# io2.net
KiCad netlist of a schematic drawn in EAGLE
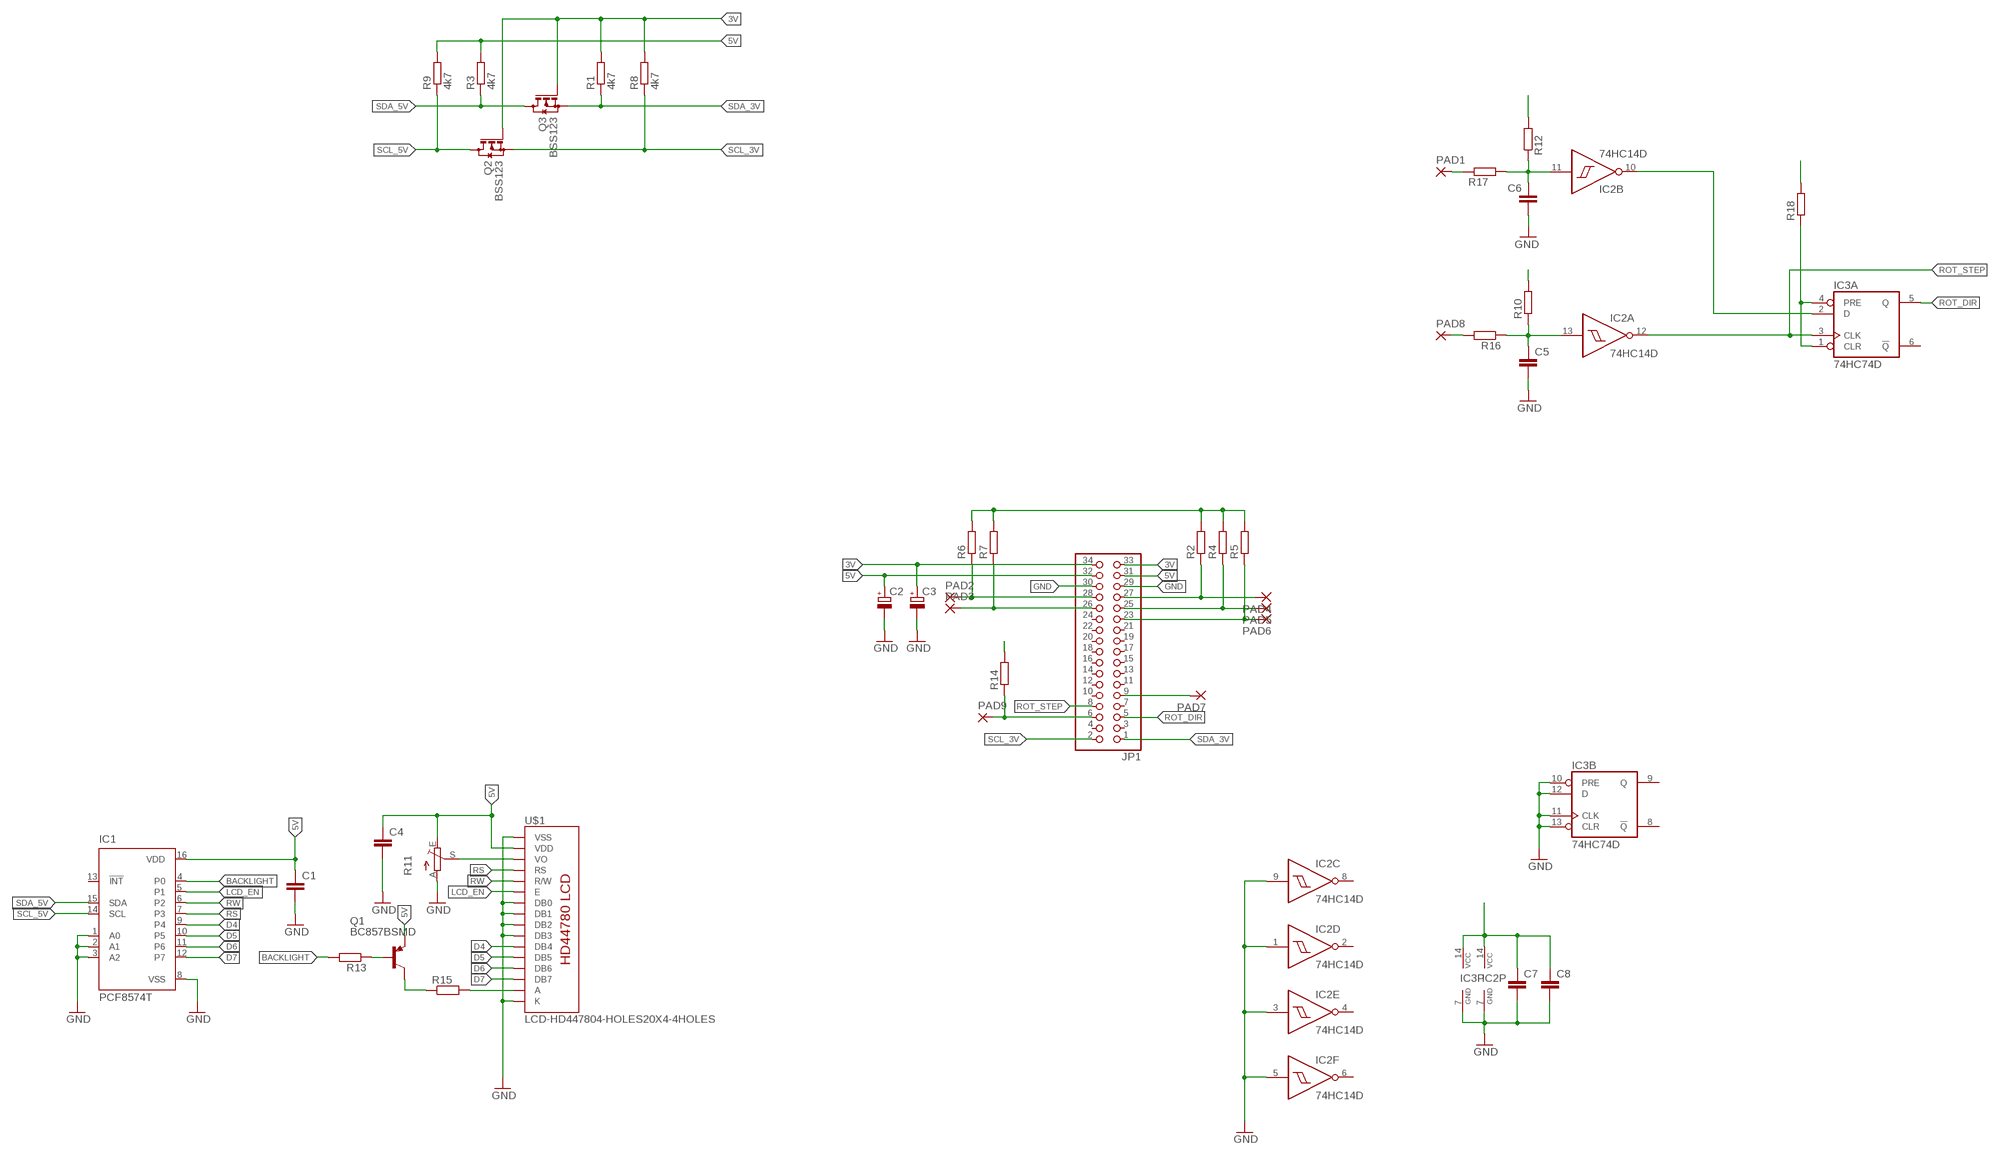
[diagram p0: schematic, sheet 1]

(export (version "E")
  (design (tool "Eeschema 10.0.6"))
  (components
    (comp (ref "C1")
      (value "C-EUC0603")
      (footprint "eagle-import:C0603")
      (libsource (lib "eagle-import") (part "C-EUC0603"))
    )
    (comp (ref "C2")
      (value "CPOL-EUSMCD")
      (footprint "eagle-import:SMC_D")
      (libsource (lib "eagle-import") (part "CPOL-EUSMCD"))
    )
    (comp (ref "C3")
      (value "CPOL-EUSMCB")
      (footprint "eagle-import:SMC_B")
      (libsource (lib "eagle-import") (part "CPOL-EUSMCB"))
    )
    (comp (ref "C4")
      (value "C-EUC1206")
      (footprint "eagle-import:C1206")
      (libsource (lib "eagle-import") (part "C-EUC1206"))
    )
    (comp (ref "C5")
      (value "C-EUC0603")
      (footprint "eagle-import:C0603")
      (libsource (lib "eagle-import") (part "C-EUC0603"))
    )
    (comp (ref "C6")
      (value "C-EUC0603")
      (footprint "eagle-import:C0603")
      (libsource (lib "eagle-import") (part "C-EUC0603"))
    )
    (comp (ref "C7")
      (value "C-EUC0603")
      (footprint "eagle-import:C0603")
      (libsource (lib "eagle-import") (part "C-EUC0603"))
    )
    (comp (ref "C8")
      (value "C-EUC0603")
      (footprint "eagle-import:C0603")
      (libsource (lib "eagle-import") (part "C-EUC0603"))
    )
    (comp (ref "IC1")
      (value "PCF8574T")
      (footprint "eagle-import:SO16W")
      (fields (field (name "MPN") "PCF8574T/3,512"))
      (libsource (lib "eagle-import") (part "PCF8574T"))
    )
    (comp (ref "IC2")
      (value "74HC14D")
      (footprint "eagle-import:SO14")
      (libsource (lib "eagle-import") (part "7414DHC"))
    )
    (comp (ref "IC3")
      (value "74HC74D")
      (footprint "eagle-import:SO14")
      (libsource (lib "eagle-import") (part "7474DHC"))
    )
    (comp (ref "JP1")
      (value "PINHD-2X17_2.54-SMD")
      (footprint "eagle-import:2X17SMD")
      (libsource (lib "eagle-import") (part "PINHD-2X17_2.54-SMD"))
    )
    (comp (ref "PAD1")
      (value "SMD2")
      (footprint "eagle-import:SMD1,27-2,54")
      (libsource (lib "eagle-import") (part "SMD2"))
    )
    (comp (ref "PAD2")
      (value "SMD2")
      (footprint "eagle-import:SMD1,27-2,54")
      (libsource (lib "eagle-import") (part "SMD2"))
    )
    (comp (ref "PAD3")
      (value "SMD2")
      (footprint "eagle-import:SMD1,27-2,54")
      (libsource (lib "eagle-import") (part "SMD2"))
    )
    (comp (ref "PAD4")
      (value "SMD2")
      (footprint "eagle-import:SMD1,27-2,54")
      (libsource (lib "eagle-import") (part "SMD2"))
    )
    (comp (ref "PAD5")
      (value "SMD2")
      (footprint "eagle-import:SMD1,27-2,54")
      (libsource (lib "eagle-import") (part "SMD2"))
    )
    (comp (ref "PAD6")
      (value "SMD2")
      (footprint "eagle-import:SMD1,27-2,54")
      (libsource (lib "eagle-import") (part "SMD2"))
    )
    (comp (ref "PAD7")
      (value "SMD2")
      (footprint "eagle-import:SMD1,27-2,54")
      (libsource (lib "eagle-import") (part "SMD2"))
    )
    (comp (ref "PAD8")
      (value "SMD2")
      (footprint "eagle-import:SMD1,27-2,54")
      (libsource (lib "eagle-import") (part "SMD2"))
    )
    (comp (ref "PAD9")
      (value "SMD2")
      (footprint "eagle-import:SMD1,27-2,54")
      (libsource (lib "eagle-import") (part "SMD2"))
    )
    (comp (ref "Q1")
      (value "BC857BSMD")
      (footprint "eagle-import:SOT23-BEC")
      (libsource (lib "eagle-import") (part "BC857SMDB"))
    )
    (comp (ref "Q2")
      (value "BSS123")
      (footprint "eagle-import:SOT23")
      (libsource (lib "eagle-import") (part "BSS123"))
    )
    (comp (ref "Q3")
      (value "BSS123")
      (footprint "eagle-import:SOT23")
      (libsource (lib "eagle-import") (part "BSS123"))
    )
    (comp (ref "R1")
      (value "4k7")
      (footprint "eagle-import:R0603")
      (libsource (lib "eagle-import") (part "R-EU_R0603"))
    )
    (comp (ref "R2")
      (value "R-EU_0204/7")
      (footprint "eagle-import:0204_7")
      (libsource (lib "eagle-import") (part "R-EU_0204/7"))
    )
    (comp (ref "R3")
      (value "4k7")
      (footprint "eagle-import:R0603")
      (libsource (lib "eagle-import") (part "R-EU_R0603"))
    )
    (comp (ref "R4")
      (value "R-EU_0204/7")
      (footprint "eagle-import:0204_7")
      (libsource (lib "eagle-import") (part "R-EU_0204/7"))
    )
    (comp (ref "R5")
      (value "R-EU_0204/7")
      (footprint "eagle-import:0204_7")
      (libsource (lib "eagle-import") (part "R-EU_0204/7"))
    )
    (comp (ref "R6")
      (value "R-EU_0204/7")
      (footprint "eagle-import:0204_7")
      (libsource (lib "eagle-import") (part "R-EU_0204/7"))
    )
    (comp (ref "R7")
      (value "R-EU_0204/7")
      (footprint "eagle-import:0204_7")
      (libsource (lib "eagle-import") (part "R-EU_0204/7"))
    )
    (comp (ref "R8")
      (value "4k7")
      (footprint "eagle-import:R0603")
      (libsource (lib "eagle-import") (part "R-EU_R0603"))
    )
    (comp (ref "R9")
      (value "4k7")
      (footprint "eagle-import:R0603")
      (libsource (lib "eagle-import") (part "R-EU_R0603"))
    )
    (comp (ref "R10")
      (value "R-EU_0204/7")
      (footprint "eagle-import:0204_7")
      (libsource (lib "eagle-import") (part "R-EU_0204/7"))
    )
    (comp (ref "R11")
      (value "TRIM_EU-B25U")
      (footprint "eagle-import:B25U")
      (libsource (lib "eagle-import") (part "TRIM_EU-B25U"))
    )
    (comp (ref "R12")
      (value "R-EU_0204/7")
      (footprint "eagle-import:0204_7")
      (libsource (lib "eagle-import") (part "R-EU_0204/7"))
    )
    (comp (ref "R13")
      (value "R-EU_0207/12")
      (footprint "eagle-import:0207_12")
      (libsource (lib "eagle-import") (part "R-EU_0207/12"))
    )
    (comp (ref "R14")
      (value "R-EU_0204/5")
      (footprint "eagle-import:0204_5")
      (libsource (lib "eagle-import") (part "R-EU_0204/5"))
    )
    (comp (ref "R15")
      (value "R-EU_R0603")
      (footprint "eagle-import:R0603")
      (libsource (lib "eagle-import") (part "R-EU_R0603"))
    )
    (comp (ref "R16")
      (value "R-EU_R0603")
      (footprint "eagle-import:R0603")
      (libsource (lib "eagle-import") (part "R-EU_R0603"))
    )
    (comp (ref "R17")
      (value "R-EU_R0603")
      (footprint "eagle-import:R0603")
      (libsource (lib "eagle-import") (part "R-EU_R0603"))
    )
    (comp (ref "R18")
      (value "R-EU_0204/7")
      (footprint "eagle-import:0204_7")
      (libsource (lib "eagle-import") (part "R-EU_0204/7"))
    )
    (comp (ref "U$1")
      (value "LCD-HD447804-HOLES20X4-4HOLES")
      (footprint "eagle-import:LCD-20X4-4HOLES")
      (libsource (lib "eagle-import") (part "LCD-HD4478020X4-4HOLES4-HOLES"))
    )
  )
  (nets
    (net (code "1") (name "3V") (class "Default")
      (node (ref "C3") (pin "+") (pinfunction "+_+") (pintype "passive"))
      (node (ref "C7") (pin "1") (pinfunction "1_1") (pintype "passive"))
      (node (ref "C8") (pin "1") (pinfunction "1_1") (pintype "passive"))
      (node (ref "IC2") (pin "14") (pinfunction "VCC_14") (pintype "power_in"))
      (node (ref "IC3") (pin "14") (pinfunction "VCC_14") (pintype "power_in"))
      (node (ref "JP1") (pin "33") (pinfunction "33_33") (pintype "passive"))
      (node (ref "JP1") (pin "34") (pinfunction "34_34") (pintype "passive"))
      (node (ref "Q2") (pin "1") (pinfunction "G_1") (pintype "passive"))
      (node (ref "Q3") (pin "1") (pinfunction "G_1") (pintype "passive"))
      (node (ref "R1") (pin "2") (pinfunction "2_2") (pintype "passive"))
      (node (ref "R10") (pin "2") (pinfunction "2_2") (pintype "passive"))
      (node (ref "R12") (pin "2") (pinfunction "2_2") (pintype "passive"))
      (node (ref "R14") (pin "2") (pinfunction "2_2") (pintype "passive"))
      (node (ref "R18") (pin "2") (pinfunction "2_2") (pintype "passive"))
      (node (ref "R2") (pin "2") (pinfunction "2_2") (pintype "passive"))
      (node (ref "R4") (pin "2") (pinfunction "2_2") (pintype "passive"))
      (node (ref "R5") (pin "2") (pinfunction "2_2") (pintype "passive"))
      (node (ref "R6") (pin "2") (pinfunction "2_2") (pintype "passive"))
      (node (ref "R7") (pin "2") (pinfunction "2_2") (pintype "passive"))
      (node (ref "R8") (pin "2") (pinfunction "2_2") (pintype "passive"))
    )
    (net (code "2") (name "5V") (class "Default")
      (node (ref "C1") (pin "1") (pinfunction "1_1") (pintype "passive"))
      (node (ref "C2") (pin "+") (pinfunction "+_+") (pintype "passive"))
      (node (ref "C4") (pin "1") (pinfunction "1_1") (pintype "passive"))
      (node (ref "IC1") (pin "16") (pinfunction "VDD_16") (pintype "power_in"))
      (node (ref "JP1") (pin "31") (pinfunction "31_31") (pintype "passive"))
      (node (ref "JP1") (pin "32") (pinfunction "32_32") (pintype "passive"))
      (node (ref "Q1") (pin "E") (pinfunction "E_E") (pintype "passive"))
      (node (ref "R11") (pin "E") (pinfunction "E_E") (pintype "passive"))
      (node (ref "R3") (pin "2") (pinfunction "2_2") (pintype "passive"))
      (node (ref "R9") (pin "2") (pinfunction "2_2") (pintype "passive"))
      (node (ref "U$1") (pin "P$2") (pinfunction "VDD_P$2") (pintype "power_in"))
    )
    (net (code "3") (name "BACKLIGHT") (class "Default")
      (node (ref "IC1") (pin "4") (pinfunction "P0_4") (pintype "bidirectional"))
      (node (ref "R13") (pin "2") (pinfunction "2_2") (pintype "passive"))
    )
    (net (code "4") (name "D4") (class "Default")
      (node (ref "IC1") (pin "9") (pinfunction "P4_9") (pintype "bidirectional"))
      (node (ref "U$1") (pin "P$11") (pinfunction "DB4_P$11") (pintype "bidirectional"))
    )
    (net (code "5") (name "D5") (class "Default")
      (node (ref "IC1") (pin "10") (pinfunction "P5_10") (pintype "bidirectional"))
      (node (ref "U$1") (pin "P$12") (pinfunction "DB5_P$12") (pintype "bidirectional"))
    )
    (net (code "6") (name "D6") (class "Default")
      (node (ref "IC1") (pin "11") (pinfunction "P6_11") (pintype "bidirectional"))
      (node (ref "U$1") (pin "P$13") (pinfunction "DB6_P$13") (pintype "bidirectional"))
    )
    (net (code "7") (name "D7") (class "Default")
      (node (ref "IC1") (pin "12") (pinfunction "P7_12") (pintype "bidirectional"))
      (node (ref "U$1") (pin "P$14") (pinfunction "DB7_P$14") (pintype "bidirectional"))
    )
    (net (code "8") (name "GND") (class "Default")
      (node (ref "C1") (pin "2") (pinfunction "2_2") (pintype "passive"))
      (node (ref "C2") (pin "-") (pinfunction "-_-") (pintype "passive"))
      (node (ref "C3") (pin "-") (pinfunction "-_-") (pintype "passive"))
      (node (ref "C4") (pin "2") (pinfunction "2_2") (pintype "passive"))
      (node (ref "C5") (pin "2") (pinfunction "2_2") (pintype "passive"))
      (node (ref "C6") (pin "2") (pinfunction "2_2") (pintype "passive"))
      (node (ref "C7") (pin "2") (pinfunction "2_2") (pintype "passive"))
      (node (ref "C8") (pin "2") (pinfunction "2_2") (pintype "passive"))
      (node (ref "IC1") (pin "1") (pinfunction "A0_1") (pintype "input"))
      (node (ref "IC1") (pin "2") (pinfunction "A1_2") (pintype "input"))
      (node (ref "IC1") (pin "3") (pinfunction "A2_3") (pintype "input"))
      (node (ref "IC1") (pin "8") (pinfunction "VSS_8") (pintype "power_in"))
      (node (ref "IC2") (pin "1") (pinfunction "I_1") (pintype "input"))
      (node (ref "IC2") (pin "3") (pinfunction "I_3") (pintype "input"))
      (node (ref "IC2") (pin "5") (pinfunction "I_5") (pintype "input"))
      (node (ref "IC2") (pin "7") (pinfunction "GND_7") (pintype "power_in"))
      (node (ref "IC2") (pin "9") (pinfunction "I_9") (pintype "input"))
      (node (ref "IC3") (pin "10") (pinfunction "PRE_10") (pintype "input"))
      (node (ref "IC3") (pin "11") (pinfunction "CLK_11") (pintype "input"))
      (node (ref "IC3") (pin "12") (pinfunction "D_12") (pintype "input"))
      (node (ref "IC3") (pin "13") (pinfunction "CLR_13") (pintype "input"))
      (node (ref "IC3") (pin "7") (pinfunction "GND_7") (pintype "power_in"))
      (node (ref "JP1") (pin "29") (pinfunction "29_29") (pintype "passive"))
      (node (ref "JP1") (pin "30") (pinfunction "30_30") (pintype "passive"))
      (node (ref "R11") (pin "A") (pinfunction "A_A") (pintype "passive"))
      (node (ref "U$1") (pin "P$1") (pinfunction "VSS_P$1") (pintype "power_in"))
      (node (ref "U$1") (pin "P$10") (pinfunction "DB3_P$10") (pintype "bidirectional"))
      (node (ref "U$1") (pin "P$16") (pinfunction "K_P$16") (pintype "power_in"))
      (node (ref "U$1") (pin "P$7") (pinfunction "DB0_P$7") (pintype "bidirectional"))
      (node (ref "U$1") (pin "P$8") (pinfunction "DB1_P$8") (pintype "bidirectional"))
      (node (ref "U$1") (pin "P$9") (pinfunction "DB2_P$9") (pintype "bidirectional"))
    )
    (net (code "9") (name "LCD_EN") (class "Default")
      (node (ref "IC1") (pin "5") (pinfunction "P1_5") (pintype "bidirectional"))
      (node (ref "U$1") (pin "P$6") (pinfunction "E_P$6") (pintype "input"))
    )
    (net (code "10") (name "Net-(IC2A-I)") (class "Default")
      (node (ref "C5") (pin "1") (pinfunction "1_1") (pintype "passive"))
      (node (ref "IC2") (pin "13") (pinfunction "I_13") (pintype "input"))
      (node (ref "R10") (pin "1") (pinfunction "1_1") (pintype "passive"))
      (node (ref "R16") (pin "1") (pinfunction "1_1") (pintype "passive"))
    )
    (net (code "11") (name "Net-(IC2B-I)") (class "Default")
      (node (ref "C6") (pin "1") (pinfunction "1_1") (pintype "passive"))
      (node (ref "IC2") (pin "11") (pinfunction "I_11") (pintype "input"))
      (node (ref "R12") (pin "1") (pinfunction "1_1") (pintype "passive"))
      (node (ref "R17") (pin "2") (pinfunction "2_2") (pintype "passive"))
    )
    (net (code "12") (name "Net-(IC2B-O)") (class "Default")
      (node (ref "IC2") (pin "10") (pinfunction "O_10") (pintype "output"))
      (node (ref "IC3") (pin "2") (pinfunction "D_2") (pintype "input"))
    )
    (net (code "13") (name "Net-(IC3A-CLR)") (class "Default")
      (node (ref "IC3") (pin "1") (pinfunction "CLR_1") (pintype "input"))
      (node (ref "IC3") (pin "4") (pinfunction "PRE_4") (pintype "input"))
      (node (ref "R18") (pin "1") (pinfunction "1_1") (pintype "passive"))
    )
    (net (code "14") (name "Net-(PAD1-P)") (class "Default")
      (node (ref "PAD1") (pin "1") (pinfunction "P_1") (pintype "passive"))
      (node (ref "R17") (pin "1") (pinfunction "1_1") (pintype "passive"))
    )
    (net (code "15") (name "Net-(PAD2-P)") (class "Default")
      (node (ref "JP1") (pin "28") (pinfunction "28_28") (pintype "passive"))
      (node (ref "PAD2") (pin "1") (pinfunction "P_1") (pintype "passive"))
      (node (ref "R6") (pin "1") (pinfunction "1_1") (pintype "passive"))
    )
    (net (code "16") (name "Net-(PAD3-P)") (class "Default")
      (node (ref "JP1") (pin "26") (pinfunction "26_26") (pintype "passive"))
      (node (ref "PAD3") (pin "1") (pinfunction "P_1") (pintype "passive"))
      (node (ref "R7") (pin "1") (pinfunction "1_1") (pintype "passive"))
    )
    (net (code "17") (name "Net-(PAD4-P)") (class "Default")
      (node (ref "JP1") (pin "27") (pinfunction "27_27") (pintype "passive"))
      (node (ref "PAD4") (pin "1") (pinfunction "P_1") (pintype "passive"))
      (node (ref "R2") (pin "1") (pinfunction "1_1") (pintype "passive"))
    )
    (net (code "18") (name "Net-(PAD5-P)") (class "Default")
      (node (ref "JP1") (pin "25") (pinfunction "25_25") (pintype "passive"))
      (node (ref "PAD5") (pin "1") (pinfunction "P_1") (pintype "passive"))
      (node (ref "R4") (pin "1") (pinfunction "1_1") (pintype "passive"))
    )
    (net (code "19") (name "Net-(PAD6-P)") (class "Default")
      (node (ref "JP1") (pin "23") (pinfunction "23_23") (pintype "passive"))
      (node (ref "PAD6") (pin "1") (pinfunction "P_1") (pintype "passive"))
      (node (ref "R5") (pin "1") (pinfunction "1_1") (pintype "passive"))
    )
    (net (code "20") (name "Net-(PAD7-P)") (class "Default")
      (node (ref "JP1") (pin "9") (pinfunction "9_9") (pintype "passive"))
      (node (ref "PAD7") (pin "1") (pinfunction "P_1") (pintype "passive"))
    )
    (net (code "21") (name "Net-(PAD8-P)") (class "Default")
      (node (ref "PAD8") (pin "1") (pinfunction "P_1") (pintype "passive"))
      (node (ref "R16") (pin "2") (pinfunction "2_2") (pintype "passive"))
    )
    (net (code "22") (name "Net-(PAD9-P)") (class "Default")
      (node (ref "JP1") (pin "6") (pinfunction "6_6") (pintype "passive"))
      (node (ref "PAD9") (pin "1") (pinfunction "P_1") (pintype "passive"))
      (node (ref "R14") (pin "1") (pinfunction "1_1") (pintype "passive"))
    )
    (net (code "23") (name "Net-(Q1-PadB)") (class "Default")
      (node (ref "Q1") (pin "B") (pinfunction "B_B") (pintype "passive"))
      (node (ref "R13") (pin "1") (pinfunction "1_1") (pintype "passive"))
    )
    (net (code "24") (name "Net-(Q1-PadC)") (class "Default")
      (node (ref "Q1") (pin "C") (pinfunction "C_C") (pintype "passive"))
      (node (ref "R15") (pin "1") (pinfunction "1_1") (pintype "passive"))
    )
    (net (code "25") (name "Net-(U$1-A)") (class "Default")
      (node (ref "R15") (pin "2") (pinfunction "2_2") (pintype "passive"))
      (node (ref "U$1") (pin "P$15") (pinfunction "A_P$15") (pintype "power_in"))
    )
    (net (code "26") (name "Net-(U$1-VO)") (class "Default")
      (node (ref "R11") (pin "S") (pinfunction "S_S") (pintype "passive"))
      (node (ref "U$1") (pin "P$3") (pinfunction "VO_P$3") (pintype "bidirectional"))
    )
    (net (code "27") (name "ROT_DIR") (class "Default")
      (node (ref "IC3") (pin "5") (pinfunction "Q_5") (pintype "output"))
      (node (ref "JP1") (pin "5") (pinfunction "5_5") (pintype "passive"))
    )
    (net (code "28") (name "ROT_STEP") (class "Default")
      (node (ref "IC2") (pin "12") (pinfunction "O_12") (pintype "output"))
      (node (ref "IC3") (pin "3") (pinfunction "CLK_3") (pintype "input"))
      (node (ref "JP1") (pin "8") (pinfunction "8_8") (pintype "passive"))
    )
    (net (code "29") (name "RS") (class "Default")
      (node (ref "IC1") (pin "7") (pinfunction "P3_7") (pintype "bidirectional"))
      (node (ref "U$1") (pin "P$4") (pinfunction "RS_P$4") (pintype "input"))
    )
    (net (code "30") (name "RW") (class "Default")
      (node (ref "IC1") (pin "6") (pinfunction "P2_6") (pintype "bidirectional"))
      (node (ref "U$1") (pin "P$5") (pinfunction "R/W_P$5") (pintype "input"))
    )
    (net (code "31") (name "SCL_3V") (class "Default")
      (node (ref "JP1") (pin "2") (pinfunction "2_2") (pintype "passive"))
      (node (ref "Q2") (pin "2") (pinfunction "S_2") (pintype "passive"))
      (node (ref "R8") (pin "1") (pinfunction "1_1") (pintype "passive"))
    )
    (net (code "32") (name "SCL_5V") (class "Default")
      (node (ref "IC1") (pin "14") (pinfunction "SCL_14") (pintype "input"))
      (node (ref "Q2") (pin "3") (pinfunction "D_3") (pintype "passive"))
      (node (ref "R9") (pin "1") (pinfunction "1_1") (pintype "passive"))
    )
    (net (code "33") (name "SDA_3V") (class "Default")
      (node (ref "JP1") (pin "1") (pinfunction "1_1") (pintype "passive"))
      (node (ref "Q3") (pin "2") (pinfunction "S_2") (pintype "passive"))
      (node (ref "R1") (pin "1") (pinfunction "1_1") (pintype "passive"))
    )
    (net (code "34") (name "SDA_5V") (class "Default")
      (node (ref "IC1") (pin "15") (pinfunction "SDA_15") (pintype "bidirectional"))
      (node (ref "Q3") (pin "3") (pinfunction "D_3") (pintype "passive"))
      (node (ref "R3") (pin "1") (pinfunction "1_1") (pintype "passive"))
    )
    (net (code "35") (name "unconnected-(IC1-~{INT}-Pad13)") (class "Default")
      (node (ref "IC1") (pin "13") (pinfunction "~{INT}_13") (pintype "output"))
    )
    (net (code "36") (name "unconnected-(IC2C-O-Pad8)") (class "Default")
      (node (ref "IC2") (pin "8") (pinfunction "O_8") (pintype "output"))
    )
    (net (code "37") (name "unconnected-(IC2D-O-Pad2)") (class "Default")
      (node (ref "IC2") (pin "2") (pinfunction "O_2") (pintype "output"))
    )
    (net (code "38") (name "unconnected-(IC2E-O-Pad4)") (class "Default")
      (node (ref "IC2") (pin "4") (pinfunction "O_4") (pintype "output"))
    )
    (net (code "39") (name "unconnected-(IC2F-O-Pad6)") (class "Default")
      (node (ref "IC2") (pin "6") (pinfunction "O_6") (pintype "output"))
    )
    (net (code "40") (name "unconnected-(IC3A-~{Q}-Pad6)") (class "Default")
      (node (ref "IC3") (pin "6") (pinfunction "~{Q}_6") (pintype "output"))
    )
    (net (code "41") (name "unconnected-(IC3B-Q-Pad9)") (class "Default")
      (node (ref "IC3") (pin "9") (pinfunction "Q_9") (pintype "output"))
    )
    (net (code "42") (name "unconnected-(IC3B-~{Q}-Pad8)") (class "Default")
      (node (ref "IC3") (pin "8") (pinfunction "~{Q}_8") (pintype "output"))
    )
    (net (code "43") (name "unconnected-(JP1-Pad3)") (class "Default")
      (node (ref "JP1") (pin "3") (pinfunction "3_3") (pintype "passive"))
    )
    (net (code "44") (name "unconnected-(JP1-Pad4)") (class "Default")
      (node (ref "JP1") (pin "4") (pinfunction "4_4") (pintype "passive"))
    )
    (net (code "45") (name "unconnected-(JP1-Pad7)") (class "Default")
      (node (ref "JP1") (pin "7") (pinfunction "7_7") (pintype "passive"))
    )
    (net (code "46") (name "unconnected-(JP1-Pad10)") (class "Default")
      (node (ref "JP1") (pin "10") (pinfunction "10_10") (pintype "passive"))
    )
    (net (code "47") (name "unconnected-(JP1-Pad11)") (class "Default")
      (node (ref "JP1") (pin "11") (pinfunction "11_11") (pintype "passive"))
    )
    (net (code "48") (name "unconnected-(JP1-Pad12)") (class "Default")
      (node (ref "JP1") (pin "12") (pinfunction "12_12") (pintype "passive"))
    )
    (net (code "49") (name "unconnected-(JP1-Pad13)") (class "Default")
      (node (ref "JP1") (pin "13") (pinfunction "13_13") (pintype "passive"))
    )
    (net (code "50") (name "unconnected-(JP1-Pad14)") (class "Default")
      (node (ref "JP1") (pin "14") (pinfunction "14_14") (pintype "passive"))
    )
    (net (code "51") (name "unconnected-(JP1-Pad15)") (class "Default")
      (node (ref "JP1") (pin "15") (pinfunction "15_15") (pintype "passive"))
    )
    (net (code "52") (name "unconnected-(JP1-Pad16)") (class "Default")
      (node (ref "JP1") (pin "16") (pinfunction "16_16") (pintype "passive"))
    )
    (net (code "53") (name "unconnected-(JP1-Pad17)") (class "Default")
      (node (ref "JP1") (pin "17") (pinfunction "17_17") (pintype "passive"))
    )
    (net (code "54") (name "unconnected-(JP1-Pad18)") (class "Default")
      (node (ref "JP1") (pin "18") (pinfunction "18_18") (pintype "passive"))
    )
    (net (code "55") (name "unconnected-(JP1-Pad19)") (class "Default")
      (node (ref "JP1") (pin "19") (pinfunction "19_19") (pintype "passive"))
    )
    (net (code "56") (name "unconnected-(JP1-Pad20)") (class "Default")
      (node (ref "JP1") (pin "20") (pinfunction "20_20") (pintype "passive"))
    )
    (net (code "57") (name "unconnected-(JP1-Pad21)") (class "Default")
      (node (ref "JP1") (pin "21") (pinfunction "21_21") (pintype "passive"))
    )
    (net (code "58") (name "unconnected-(JP1-Pad22)") (class "Default")
      (node (ref "JP1") (pin "22") (pinfunction "22_22") (pintype "passive"))
    )
    (net (code "59") (name "unconnected-(JP1-Pad24)") (class "Default")
      (node (ref "JP1") (pin "24") (pinfunction "24_24") (pintype "passive"))
    )
  )
)
